# AmbaSat-02-STS21.net
KiCad netlist of a schematic drawn in EAGLE
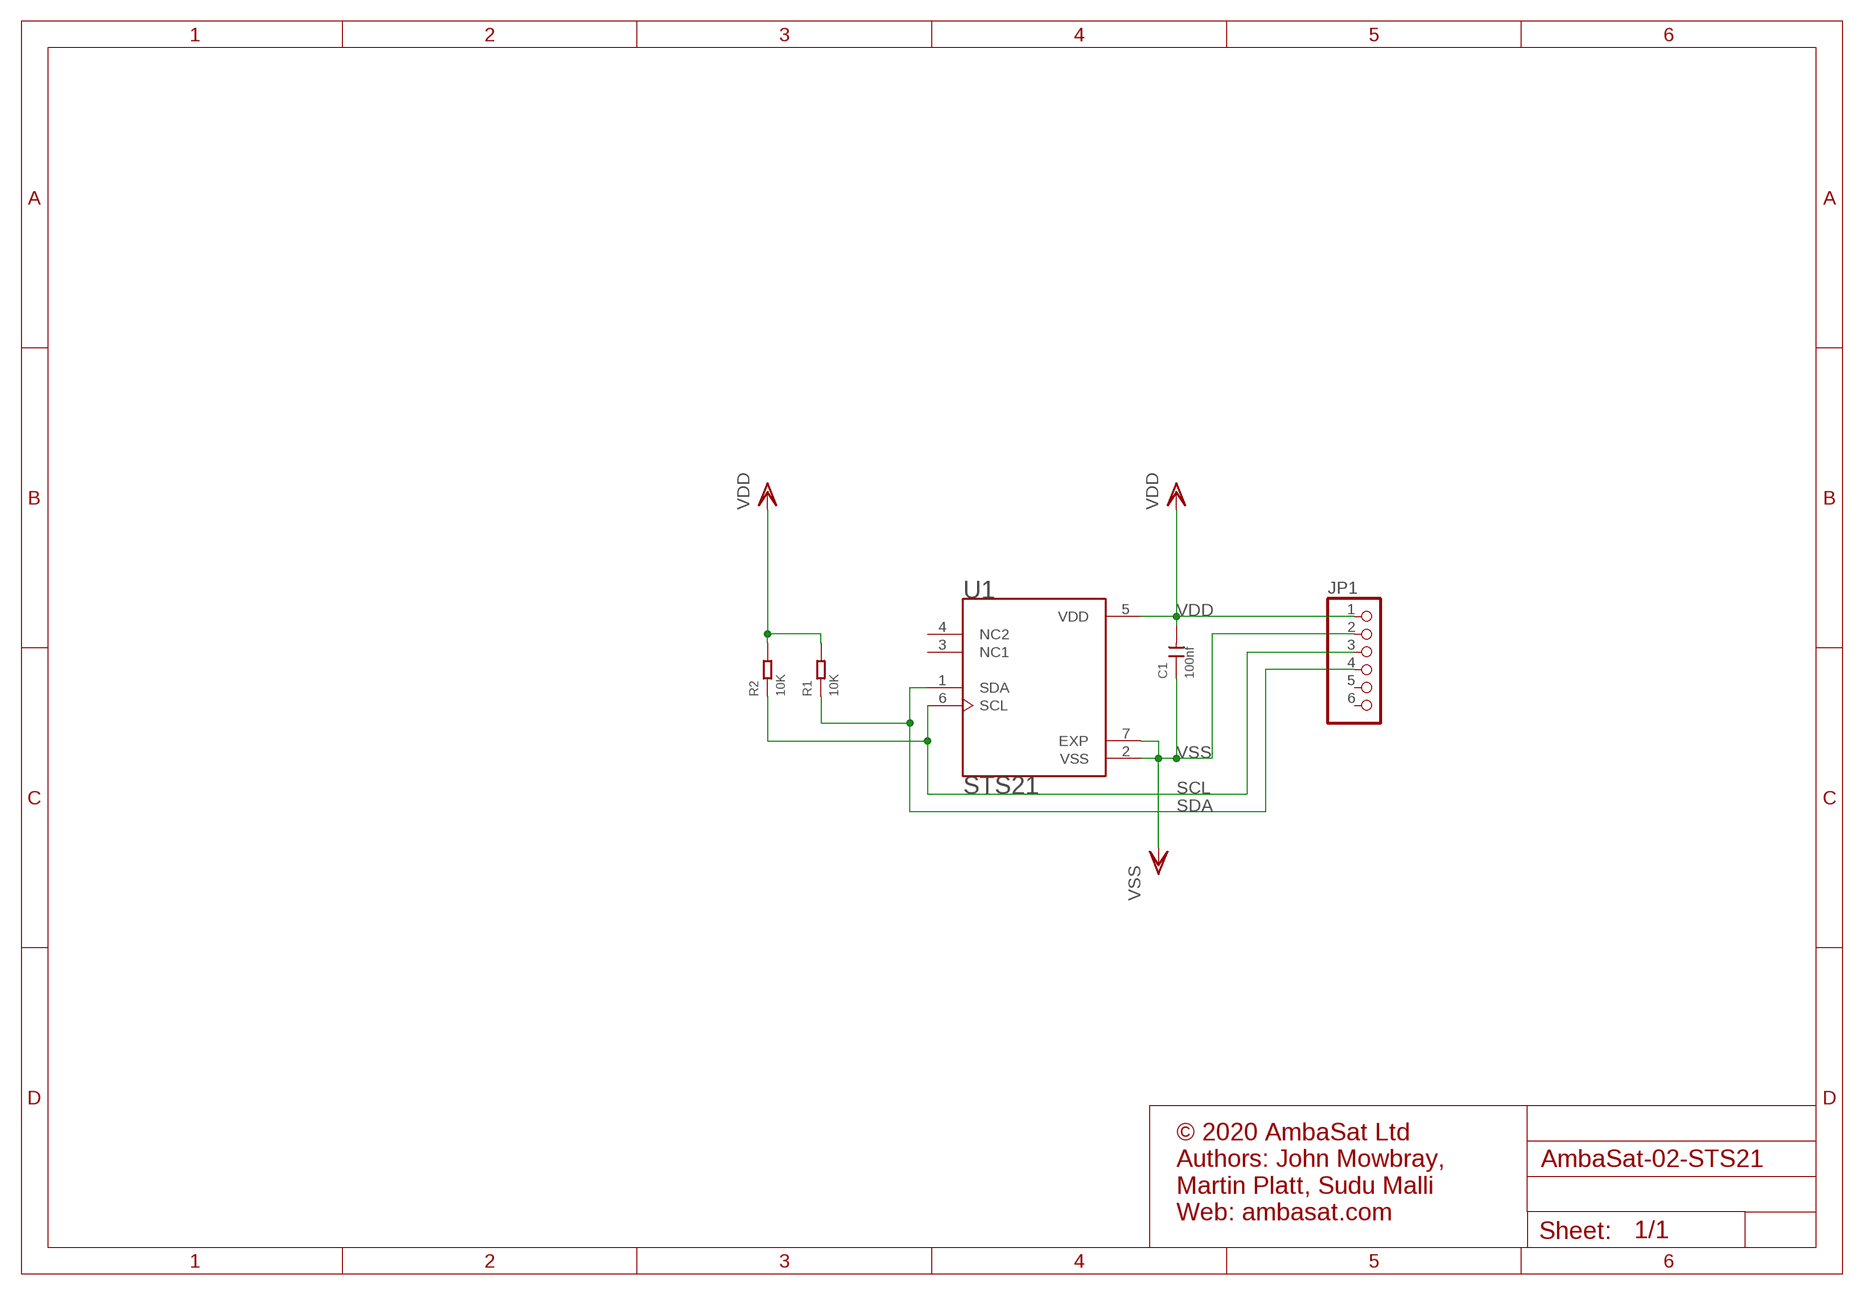
[diagram p0: schematic, sheet 1]

(export (version "E")
  (design (tool "Eeschema 10.0.6"))
  (components
    (comp (ref "C1")
      (value "100nf")
      (footprint "eagle-import:C0805")
      (fields (field (name "MPN") "CC0805KRX7R9BB104"))
      (libsource (lib "eagle-import") (part "CERAMIC-100NF-50V-10%-X7R(0805)"))
    )
    (comp (ref "JP1")
      (value "HEADER-1X6")
      (footprint "eagle-import:1X06_OVAL")
      (libsource (lib "eagle-import") (part "HEADER-1X6"))
    )
    (comp (ref "R1")
      (value "10K")
      (footprint "eagle-import:R0805")
      (fields (field (name "MPN") "RC0805FR-0710KL"))
      (libsource (lib "eagle-import") (part "SMD-RES-10K-1%-1/8W(0805)"))
    )
    (comp (ref "R2")
      (value "10K")
      (footprint "eagle-import:R0805")
      (fields (field (name "MPN") "RC0805FR-0710KL"))
      (libsource (lib "eagle-import") (part "SMD-RES-10K-1%-1/8W(0805)"))
    )
    (comp (ref "U1")
      (value "STS21")
      (footprint "eagle-import:XDCR_SGP30-2.5K")
      (libsource (lib "eagle-import") (part "STS21"))
    )
  )
  (nets
    (net (code "1") (name "/SCL") (class "Default")
      (node (ref "JP1") (pin "3") (pinfunction "3_3") (pintype "passive"))
      (node (ref "R2") (pin "1") (pinfunction "1_1") (pintype "passive"))
      (node (ref "U1") (pin "6") (pinfunction "SCL_6") (pintype "bidirectional"))
    )
    (net (code "2") (name "/SDA") (class "Default")
      (node (ref "JP1") (pin "4") (pinfunction "4_4") (pintype "passive"))
      (node (ref "R1") (pin "1") (pinfunction "1_1") (pintype "passive"))
      (node (ref "U1") (pin "1") (pinfunction "SDA_1") (pintype "bidirectional"))
    )
    (net (code "3") (name "VDD") (class "Default")
      (node (ref "C1") (pin "2") (pinfunction "2_2") (pintype "passive"))
      (node (ref "JP1") (pin "1") (pinfunction "1_1") (pintype "passive"))
      (node (ref "R1") (pin "2") (pinfunction "2_2") (pintype "passive"))
      (node (ref "R2") (pin "2") (pinfunction "2_2") (pintype "passive"))
      (node (ref "U1") (pin "5") (pinfunction "VDD_5") (pintype "power_in"))
    )
    (net (code "4") (name "VSS") (class "Default")
      (node (ref "C1") (pin "1") (pinfunction "1_1") (pintype "passive"))
      (node (ref "JP1") (pin "2") (pinfunction "2_2") (pintype "passive"))
      (node (ref "U1") (pin "2") (pinfunction "VSS_2") (pintype "passive"))
      (node (ref "U1") (pin "7") (pinfunction "EXP_7") (pintype "passive"))
    )
    (net (code "5") (name "unconnected-(JP1-Pad5)") (class "Default")
      (node (ref "JP1") (pin "5") (pinfunction "5_5") (pintype "passive"))
    )
    (net (code "6") (name "unconnected-(JP1-Pad6)") (class "Default")
      (node (ref "JP1") (pin "6") (pinfunction "6_6") (pintype "passive"))
    )
    (net (code "7") (name "unconnected-(U1-NC1-Pad3)") (class "Default")
      (node (ref "U1") (pin "3") (pinfunction "NC1_3") (pintype "input"))
    )
    (net (code "8") (name "unconnected-(U1-NC2-Pad4)") (class "Default")
      (node (ref "U1") (pin "4") (pinfunction "NC2_4") (pintype "input"))
    )
  )
)
